# HV_Piezo_Driver.net
KiCad netlist of a schematic drawn in Altium Designer
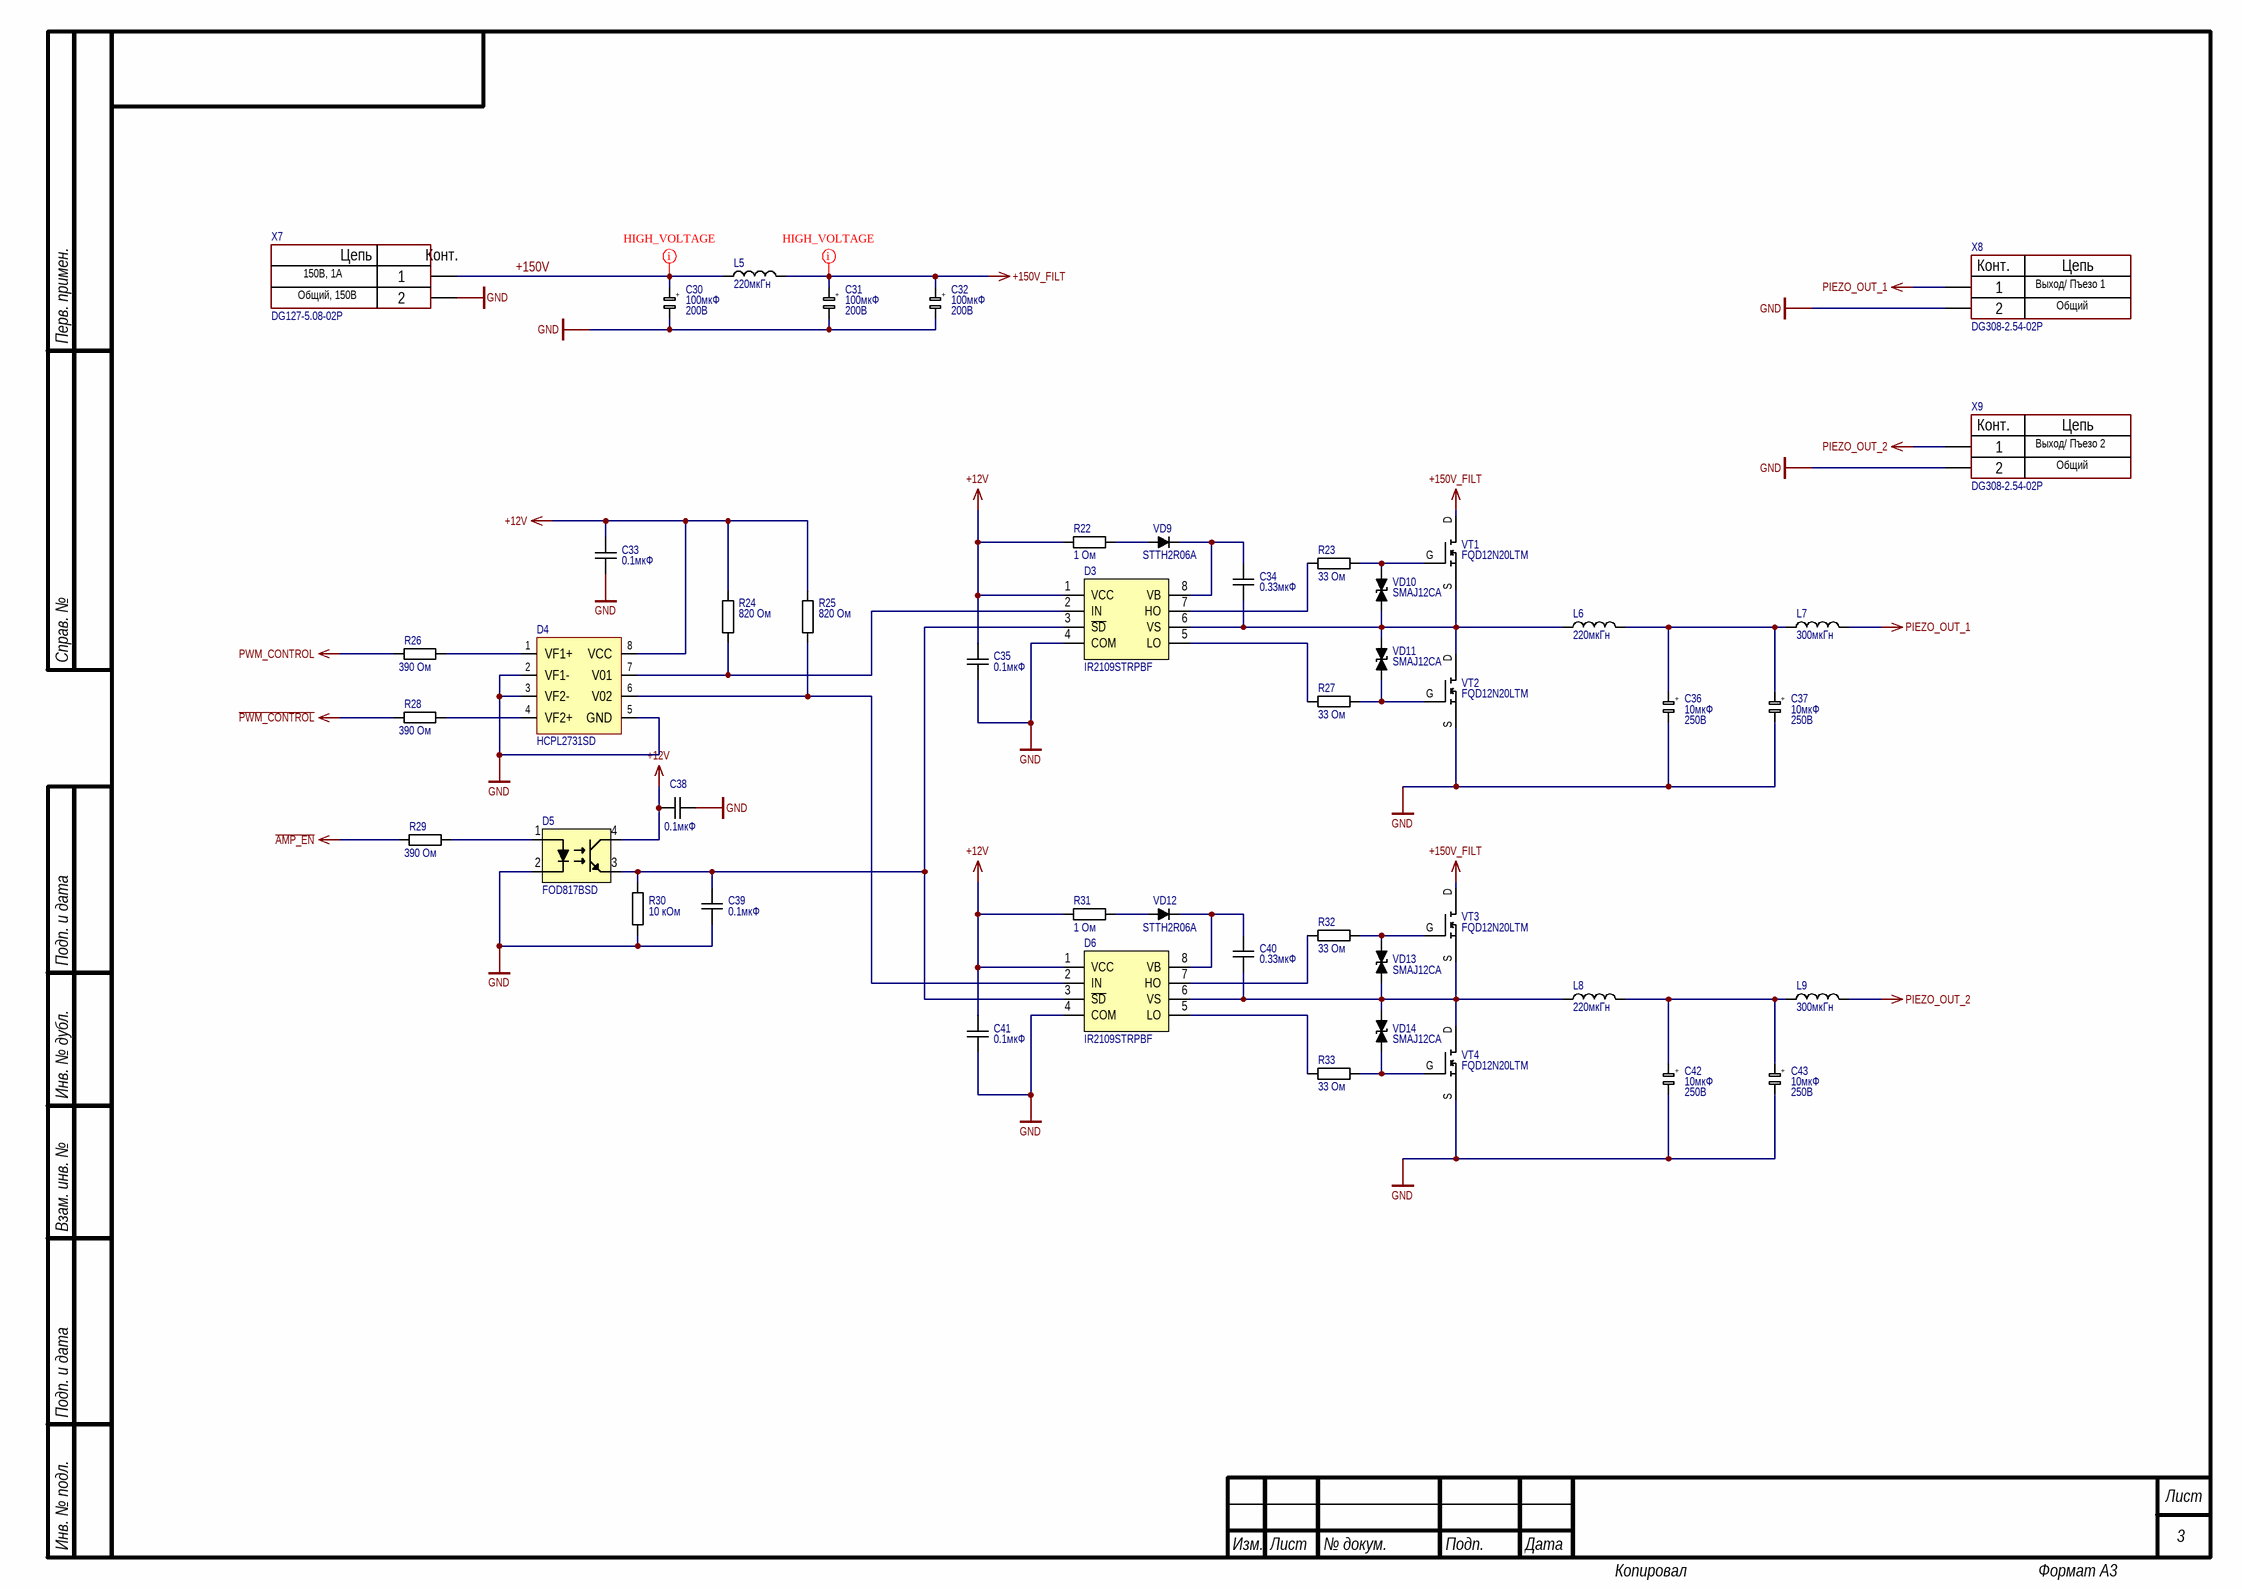
[diagram p0: HV_Piezo_Driver.SchDoc]

(export (version "E")
  (design (tool "Eeschema 10.0.6"))
  (components
    (comp (ref "C30")
      (value "100мкФ")
      (footprint "PiezoControlBoard:CAP_RADIAL_13x17_P5")
      (fields
        (field (name "TOLERANCE") "20%")
        (field (name "VOLTAGE") "200В")
        (field (name "MANUFACTURER PART NUMBER") "JRB2D101M05001300250000B")
        (field (name "Comment") "CAP-100мкФ-20%-200В-105°C-Radial")
      )
      (libsource (lib "PiezoControlBoard") (part "JRB2D101M05001300250000B"))
    )
    (comp (ref "C31")
      (value "100мкФ")
      (footprint "PiezoControlBoard:CAP_RADIAL_13x17_P5")
      (fields
        (field (name "TOLERANCE") "20%")
        (field (name "VOLTAGE") "200В")
        (field (name "MANUFACTURER PART NUMBER") "JRB2D101M05001300250000B")
        (field (name "Comment") "CAP-100мкФ-20%-200В-105°C-Radial")
      )
      (libsource (lib "PiezoControlBoard") (part "JRB2D101M05001300250000B"))
    )
    (comp (ref "C32")
      (value "100мкФ")
      (footprint "PiezoControlBoard:CAP_RADIAL_13x17_P5")
      (fields
        (field (name "TOLERANCE") "20%")
        (field (name "VOLTAGE") "200В")
        (field (name "MANUFACTURER PART NUMBER") "JRB2D101M05001300250000B")
        (field (name "Comment") "CAP-100мкФ-20%-200В-105°C-Radial")
      )
      (libsource (lib "PiezoControlBoard") (part "JRB2D101M05001300250000B"))
    )
    (comp (ref "C33")
      (value "0.1мкФ")
      (footprint "CAP-0603")
      (description "Конденсатор")
      (fields (field (name "TOLERANCE") "10%") (field (name "VOLTAGE") "50В"))
      (libsource (lib "load") (part "Cap_0603"))
    )
    (comp (ref "C34")
      (value "0.33мкФ")
      (footprint "CAP-0805")
      (description "Конденсатор")
      (fields (field (name "TOLERANCE") "10%") (field (name "VOLTAGE") "25В"))
      (libsource (lib "load") (part "Cap_0805"))
    )
    (comp (ref "C35")
      (value "0.1мкФ")
      (footprint "CAP-0603")
      (description "Конденсатор")
      (fields (field (name "TOLERANCE") "10%") (field (name "VOLTAGE") "50В"))
      (libsource (lib "load") (part "Cap_0603"))
    )
    (comp (ref "C36")
      (value "10мкФ")
      (footprint "PiezoControlBoard:CAP_RADIAL_10x20_P5")
      (fields
        (field (name "TOLERANCE") "20%")
        (field (name "MANUFACTURER PART NUMBER") "JRB2E100M05001000170000B")
        (field (name "VOLTAGE") "250В")
        (field (name "Comment") "CAP-10мкФ-20%-250В-105°C-Radial")
      )
      (libsource (lib "PiezoControlBoard") (part "JRB2E100M05001000170000B"))
    )
    (comp (ref "C37")
      (value "10мкФ")
      (footprint "PiezoControlBoard:CAP_RADIAL_10x20_P5")
      (fields
        (field (name "TOLERANCE") "20%")
        (field (name "MANUFACTURER PART NUMBER") "JRB2E100M05001000170000B")
        (field (name "VOLTAGE") "250В")
        (field (name "Comment") "CAP-10мкФ-20%-250В-105°C-Radial")
      )
      (libsource (lib "PiezoControlBoard") (part "JRB2E100M05001000170000B"))
    )
    (comp (ref "C38")
      (value "0.1мкФ")
      (footprint "CAP-0603")
      (description "Конденсатор")
      (fields (field (name "TOLERANCE") "10%") (field (name "VOLTAGE") "50В"))
      (libsource (lib "load") (part "Cap_0603"))
    )
    (comp (ref "C39")
      (value "0.1мкФ")
      (footprint "CAP-0603")
      (description "Конденсатор")
      (fields (field (name "TOLERANCE") "10%") (field (name "VOLTAGE") "50В"))
      (libsource (lib "load") (part "Cap_0603"))
    )
    (comp (ref "C40")
      (value "0.33мкФ")
      (footprint "CAP-0805")
      (description "Конденсатор")
      (fields (field (name "TOLERANCE") "10%") (field (name "VOLTAGE") "25В"))
      (libsource (lib "load") (part "Cap_0805"))
    )
    (comp (ref "C41")
      (value "0.1мкФ")
      (footprint "CAP-0603")
      (description "Конденсатор")
      (fields (field (name "TOLERANCE") "10%") (field (name "VOLTAGE") "50В"))
      (libsource (lib "load") (part "Cap_0603"))
    )
    (comp (ref "C42")
      (value "10мкФ")
      (footprint "PiezoControlBoard:CAP_RADIAL_10x20_P5")
      (fields
        (field (name "TOLERANCE") "20%")
        (field (name "MANUFACTURER PART NUMBER") "JRB2E100M05001000170000B")
        (field (name "VOLTAGE") "250В")
        (field (name "Comment") "CAP-10мкФ-20%-250В-105°C-Radial")
      )
      (libsource (lib "PiezoControlBoard") (part "JRB2E100M05001000170000B"))
    )
    (comp (ref "C43")
      (value "10мкФ")
      (footprint "PiezoControlBoard:CAP_RADIAL_10x20_P5")
      (fields
        (field (name "TOLERANCE") "20%")
        (field (name "MANUFACTURER PART NUMBER") "JRB2E100M05001000170000B")
        (field (name "VOLTAGE") "250В")
        (field (name "Comment") "CAP-10мкФ-20%-250В-105°C-Radial")
      )
      (libsource (lib "PiezoControlBoard") (part "JRB2E100M05001000170000B"))
    )
    (comp (ref "D3")
      (value "IR2109STRPBF")
      (footprint "PiezoControlBoard:SOIC-8")
      (description "Драйвер полумостовой")
      (fields (field (name "POWER") "625mW"))
      (libsource (lib "PiezoControlBoard") (part "IR2109STRPBF"))
    )
    (comp (ref "D4")
      (value "HCPL2731SD")
      (footprint "PiezoControlBoard:SMD-8")
      (description "Оптоизолятор 2.5кВ двухканальный с транзистором Дарлингтона 8SMD")
      (libsource (lib "PiezoControlBoard") (part "HCPL2731SD"))
    )
    (comp (ref "D5")
      (value "FOD817BSD")
      (footprint "PiezoControlBoard:SMD-4")
      (description "Optocoupler, Transistor Output, 1 Channel, Surface Mount DIP, 4 Pins, 50 mA, 5 kV, 130 %")
      (fields (field (name "MANUFACTURER") "onsemi"))
      (libsource (lib "PiezoControlBoard") (part "FOD817BSD"))
    )
    (comp (ref "D6")
      (value "IR2109STRPBF")
      (footprint "PiezoControlBoard:SOIC-8")
      (description "Драйвер полумостовой")
      (fields (field (name "POWER") "625mW"))
      (libsource (lib "PiezoControlBoard") (part "IR2109STRPBF"))
    )
    (comp (ref "L5")
      (value "SPRH127-221M")
      (footprint "PiezoControlBoard:IND_12.3X12.3")
      (description "220мкГн, 2.22А, 12.3х12.3х8 мм, Катушка индуктивности SMD")
      (fields (field (name "INDUCTANCE") "220мкГн"))
      (libsource (lib "PiezoControlBoard") (part "SPRH127-221M"))
    )
    (comp (ref "L6")
      (value "SPRH127-221M")
      (footprint "PiezoControlBoard:IND_12.3X12.3")
      (description "220мкГн, 2.22А, 12.3х12.3х8 мм, Катушка индуктивности SMD")
      (fields (field (name "INDUCTANCE") "220мкГн"))
      (libsource (lib "PiezoControlBoard") (part "SPRH127-221M"))
    )
    (comp (ref "L7")
      (value "SDR0805-331KL")
      (footprint "PiezoControlBoard:IND_7.8X7.8")
      (description "330мкГн, 0.4А, Индуктивность SMD")
      (fields (field (name "INDUCTANCE") "300мкГн"))
      (libsource (lib "PiezoControlBoard") (part "SDR0805-331KL"))
    )
    (comp (ref "L8")
      (value "SPRH127-221M")
      (footprint "PiezoControlBoard:IND_12.3X12.3")
      (description "220мкГн, 2.22А, 12.3х12.3х8 мм, Катушка индуктивности SMD")
      (fields (field (name "INDUCTANCE") "220мкГн"))
      (libsource (lib "PiezoControlBoard") (part "SPRH127-221M"))
    )
    (comp (ref "L9")
      (value "SDR0805-331KL")
      (footprint "PiezoControlBoard:IND_7.8X7.8")
      (description "330мкГн, 0.4А, Индуктивность SMD")
      (fields (field (name "INDUCTANCE") "300мкГн"))
      (libsource (lib "PiezoControlBoard") (part "SDR0805-331KL"))
    )
    (comp (ref "R22")
      (value "1 Ом")
      (footprint "RES-1206")
      (description "Резистор")
      (fields (field (name "TOLERANCE") "5%") (field (name "POWER") "0.25Вт"))
      (libsource (lib "load") (part "Res_1206"))
    )
    (comp (ref "R23")
      (value "33 Ом")
      (footprint "RES-1206")
      (description "Резистор")
      (fields (field (name "TOLERANCE") "5%") (field (name "POWER") "0,25Вт"))
      (libsource (lib "load") (part "Res_1206"))
    )
    (comp (ref "R24")
      (value "820 Ом")
      (footprint "RES-1206")
      (description "Резистор")
      (fields (field (name "TOLERANCE") "5%") (field (name "POWER") "0.25Вт"))
      (libsource (lib "load") (part "Res_1206"))
    )
    (comp (ref "R25")
      (value "820 Ом")
      (footprint "RES-1206")
      (description "Резистор")
      (fields (field (name "TOLERANCE") "5%") (field (name "POWER") "0.25Вт"))
      (libsource (lib "load") (part "Res_1206"))
    )
    (comp (ref "R26")
      (value "390 Ом")
      (footprint "RES-0603")
      (description "Резистор")
      (fields (field (name "POWER") "250мВт") (field (name "TOLERANCE") "5%"))
      (libsource (lib "load") (part "Res_0603"))
    )
    (comp (ref "R27")
      (value "33 Ом")
      (footprint "RES-1206")
      (description "Резистор")
      (fields (field (name "TOLERANCE") "5%") (field (name "POWER") "0,25Вт"))
      (libsource (lib "load") (part "Res_1206"))
    )
    (comp (ref "R28")
      (value "390 Ом")
      (footprint "RES-0603")
      (description "Резистор")
      (fields (field (name "POWER") "250мВт") (field (name "TOLERANCE") "5%"))
      (libsource (lib "load") (part "Res_0603"))
    )
    (comp (ref "R29")
      (value "390 Ом")
      (footprint "RES-0603")
      (description "Резистор")
      (fields (field (name "POWER") "250мВт") (field (name "TOLERANCE") "5%"))
      (libsource (lib "load") (part "Res_0603"))
    )
    (comp (ref "R30")
      (value "10 кОм")
      (footprint "RES-0603")
      (description "Резистор")
      (fields (field (name "POWER") "0.1Вт") (field (name "TOLERANCE") "5%"))
      (libsource (lib "load") (part "Res_0603"))
    )
    (comp (ref "R31")
      (value "1 Ом")
      (footprint "RES-1206")
      (description "Резистор")
      (fields (field (name "TOLERANCE") "5%") (field (name "POWER") "0.25Вт"))
      (libsource (lib "load") (part "Res_1206"))
    )
    (comp (ref "R32")
      (value "33 Ом")
      (footprint "RES-1206")
      (description "Резистор")
      (fields (field (name "TOLERANCE") "5%") (field (name "POWER") "0,25Вт"))
      (libsource (lib "load") (part "Res_1206"))
    )
    (comp (ref "R33")
      (value "33 Ом")
      (footprint "RES-1206")
      (description "Резистор")
      (fields (field (name "TOLERANCE") "5%") (field (name "POWER") "0,25Вт"))
      (libsource (lib "load") (part "Res_1206"))
    )
    (comp (ref "VD9")
      (value "STTH2R06A")
      (footprint "PiezoControlBoard:SMA")
      (description "Rectifier Diode, 1 Phase, 1 Element, 2A, 600V V(RRM), Silicon")
      (fields (field (name "MANUFACTURER") "STMicroelectronics"))
      (libsource (lib "PiezoControlBoard") (part "STTH2R06A"))
    )
    (comp (ref "VD10")
      (value "SMAJ12CA")
      (footprint "PiezoControlBoard:DO-214AC")
      (description "Диод защитный от перенапряжения - TVS (супрессор) 12В включение 19.9В ограничение SMA")
      (libsource (lib "PiezoControlBoard") (part "SMAJ12CA"))
    )
    (comp (ref "VD11")
      (value "SMAJ12CA")
      (footprint "PiezoControlBoard:DO-214AC")
      (description "Диод защитный от перенапряжения - TVS (супрессор) 12В включение 19.9В ограничение SMA")
      (libsource (lib "PiezoControlBoard") (part "SMAJ12CA"))
    )
    (comp (ref "VD12")
      (value "STTH2R06A")
      (footprint "PiezoControlBoard:SMA")
      (description "Rectifier Diode, 1 Phase, 1 Element, 2A, 600V V(RRM), Silicon")
      (fields (field (name "MANUFACTURER") "STMicroelectronics"))
      (libsource (lib "PiezoControlBoard") (part "STTH2R06A"))
    )
    (comp (ref "VD13")
      (value "SMAJ12CA")
      (footprint "PiezoControlBoard:DO-214AC")
      (description "Диод защитный от перенапряжения - TVS (супрессор) 12В включение 19.9В ограничение SMA")
      (libsource (lib "PiezoControlBoard") (part "SMAJ12CA"))
    )
    (comp (ref "VD14")
      (value "SMAJ12CA")
      (footprint "PiezoControlBoard:DO-214AC")
      (description "Диод защитный от перенапряжения - TVS (супрессор) 12В включение 19.9В ограничение SMA")
      (libsource (lib "PiezoControlBoard") (part "SMAJ12CA"))
    )
    (comp (ref "VT1")
      (value "FQD12N20LTM")
      (footprint "PiezoControlBoard:DPAK3")
      (libsource (lib "PiezoControlBoard") (part "FQD12N20LTM"))
    )
    (comp (ref "VT2")
      (value "FQD12N20LTM")
      (footprint "PiezoControlBoard:DPAK3")
      (libsource (lib "PiezoControlBoard") (part "FQD12N20LTM"))
    )
    (comp (ref "VT3")
      (value "FQD12N20LTM")
      (footprint "PiezoControlBoard:DPAK3")
      (libsource (lib "PiezoControlBoard") (part "FQD12N20LTM"))
    )
    (comp (ref "VT4")
      (value "FQD12N20LTM")
      (footprint "PiezoControlBoard:DPAK3")
      (libsource (lib "PiezoControlBoard") (part "FQD12N20LTM"))
    )
    (comp (ref "X7")
      (value "DG127-5.08-02P")
      (footprint "PiezoControlBoard:DG12750802P141000AH")
      (fields (field (name "CURCIUT 2") "Общий, 150В") (field (name "CURCIUT 1") "150В, 1А"))
      (libsource (lib "PiezoControlBoard") (part "DG127-5.08-02P"))
    )
    (comp (ref "X8")
      (value "DG308-2.54-02P")
      (footprint "PiezoControlBoard:DG30825402P1400AH")
      (fields (field (name "CURCIUT 2") "Общий") (field (name "CURCIUT 1") "Выход/ Пъезо 1"))
      (libsource (lib "PiezoControlBoard") (part "DG308-2.54-02P"))
    )
    (comp (ref "X9")
      (value "DG308-2.54-02P")
      (footprint "PiezoControlBoard:DG30825402P1400AH")
      (fields (field (name "CURCIUT 2") "Общий") (field (name "CURCIUT 1") "Выход/ Пъезо 2"))
      (libsource (lib "PiezoControlBoard") (part "DG308-2.54-02P"))
    )
  )
  (nets
    (net (code "1") (name "+12V") (class "Default")
      (node (ref "C33") (pin "2") (pinfunction "2_2") (pintype "passive"))
      (node (ref "C35") (pin "2") (pinfunction "2_2") (pintype "passive"))
      (node (ref "C38") (pin "2") (pinfunction "2_2") (pintype "passive"))
      (node (ref "C41") (pin "2") (pinfunction "2_2") (pintype "passive"))
      (node (ref "D3") (pin "1") (pinfunction "VCC_1") (pintype "power_in"))
      (node (ref "D4") (pin "8") (pinfunction "VCC_8") (pintype "passive"))
      (node (ref "D5") (pin "4") (pinfunction "COLLECTOR_4") (pintype "passive"))
      (node (ref "D6") (pin "1") (pinfunction "VCC_1") (pintype "power_in"))
      (node (ref "R22") (pin "1") (pinfunction "1_1") (pintype "passive"))
      (node (ref "R24") (pin "2") (pinfunction "2_2") (pintype "passive"))
      (node (ref "R25") (pin "2") (pinfunction "2_2") (pintype "passive"))
      (node (ref "R31") (pin "1") (pinfunction "1_1") (pintype "passive"))
    )
    (net (code "2") (name "+150V_FILT") (class "Default")
      (node (ref "C31") (pin "P") (pinfunction "P_P") (pintype "passive"))
      (node (ref "C32") (pin "P") (pinfunction "P_P") (pintype "passive"))
      (node (ref "L5") (pin "2") (pinfunction "2_2") (pintype "passive"))
      (node (ref "VT1") (pin "D") (pinfunction "D_D") (pintype "passive"))
      (node (ref "VT3") (pin "D") (pinfunction "D_D") (pintype "passive"))
    )
    (net (code "3") (name "/+150V") (class "Default")
      (node (ref "C30") (pin "P") (pinfunction "P_P") (pintype "passive"))
      (node (ref "L5") (pin "1") (pinfunction "1_1") (pintype "passive"))
      (node (ref "X7") (pin "1") (pinfunction "1_1") (pintype "passive"))
    )
    (net (code "4") (name "GND") (class "Default")
      (node (ref "C30") (pin "N") (pinfunction "N_N") (pintype "passive"))
      (node (ref "C31") (pin "N") (pinfunction "N_N") (pintype "passive"))
      (node (ref "C32") (pin "N") (pinfunction "N_N") (pintype "passive"))
      (node (ref "C33") (pin "1") (pinfunction "1_1") (pintype "passive"))
      (node (ref "C35") (pin "1") (pinfunction "1_1") (pintype "passive"))
      (node (ref "C36") (pin "N") (pinfunction "N_N") (pintype "passive"))
      (node (ref "C37") (pin "N") (pinfunction "N_N") (pintype "passive"))
      (node (ref "C38") (pin "1") (pinfunction "1_1") (pintype "passive"))
      (node (ref "C39") (pin "1") (pinfunction "1_1") (pintype "passive"))
      (node (ref "C41") (pin "1") (pinfunction "1_1") (pintype "passive"))
      (node (ref "C42") (pin "N") (pinfunction "N_N") (pintype "passive"))
      (node (ref "C43") (pin "N") (pinfunction "N_N") (pintype "passive"))
      (node (ref "D3") (pin "4") (pinfunction "COM_4") (pintype "passive"))
      (node (ref "D4") (pin "2") (pinfunction "VF1-_2") (pintype "passive"))
      (node (ref "D4") (pin "3") (pinfunction "VF2-_3") (pintype "passive"))
      (node (ref "D4") (pin "5") (pinfunction "GND_5") (pintype "passive"))
      (node (ref "D5") (pin "2") (pinfunction "CATHODE_2") (pintype "passive"))
      (node (ref "D6") (pin "4") (pinfunction "COM_4") (pintype "passive"))
      (node (ref "R30") (pin "1") (pinfunction "1_1") (pintype "passive"))
      (node (ref "VT2") (pin "S") (pinfunction "S_S") (pintype "passive"))
      (node (ref "VT4") (pin "S") (pinfunction "S_S") (pintype "passive"))
      (node (ref "X7") (pin "2") (pinfunction "2_2") (pintype "passive"))
      (node (ref "X8") (pin "2") (pinfunction "2_2") (pintype "passive"))
      (node (ref "X9") (pin "2") (pinfunction "2_2") (pintype "passive"))
    )
    (net (code "5") (name "Net-(C36-PadP)") (class "Default")
      (node (ref "C36") (pin "P") (pinfunction "P_P") (pintype "passive"))
      (node (ref "C37") (pin "P") (pinfunction "P_P") (pintype "passive"))
      (node (ref "L6") (pin "2") (pinfunction "2_2") (pintype "passive"))
      (node (ref "L7") (pin "1") (pinfunction "1_1") (pintype "passive"))
    )
    (net (code "6") (name "Net-(C42-PadP)") (class "Default")
      (node (ref "C42") (pin "P") (pinfunction "P_P") (pintype "passive"))
      (node (ref "C43") (pin "P") (pinfunction "P_P") (pintype "passive"))
      (node (ref "L8") (pin "2") (pinfunction "2_2") (pintype "passive"))
      (node (ref "L9") (pin "1") (pinfunction "1_1") (pintype "passive"))
    )
    (net (code "7") (name "Net-(D3-HO)") (class "Default")
      (node (ref "D3") (pin "7") (pinfunction "HO_7") (pintype "passive"))
      (node (ref "R23") (pin "1") (pinfunction "1_1") (pintype "passive"))
    )
    (net (code "8") (name "Net-(D3-IN)") (class "Default")
      (node (ref "D3") (pin "2") (pinfunction "IN_2") (pintype "passive"))
      (node (ref "D4") (pin "7") (pinfunction "V01_7") (pintype "passive"))
      (node (ref "R24") (pin "1") (pinfunction "1_1") (pintype "passive"))
    )
    (net (code "9") (name "Net-(D3-LO)") (class "Default")
      (node (ref "D3") (pin "5") (pinfunction "LO_5") (pintype "passive"))
      (node (ref "R27") (pin "1") (pinfunction "1_1") (pintype "passive"))
    )
    (net (code "10") (name "Net-(D3-VB)") (class "Default")
      (node (ref "C34") (pin "2") (pinfunction "2_2") (pintype "passive"))
      (node (ref "D3") (pin "8") (pinfunction "VB_8") (pintype "passive"))
      (node (ref "VD9") (pin "2") (pinfunction "A_2") (pintype "passive"))
    )
    (net (code "11") (name "Net-(D3-VS)") (class "Default")
      (node (ref "C34") (pin "1") (pinfunction "1_1") (pintype "passive"))
      (node (ref "D3") (pin "6") (pinfunction "VS_6") (pintype "passive"))
      (node (ref "L6") (pin "1") (pinfunction "1_1") (pintype "passive"))
      (node (ref "VD10") (pin "C") (pinfunction "C_C") (pintype "passive"))
      (node (ref "VD11") (pin "A") (pinfunction "A_A") (pintype "passive"))
      (node (ref "VT1") (pin "S") (pinfunction "S_S") (pintype "passive"))
      (node (ref "VT2") (pin "D") (pinfunction "D_D") (pintype "passive"))
    )
    (net (code "12") (name "Net-(D3-~{SD})") (class "Default")
      (node (ref "C39") (pin "2") (pinfunction "2_2") (pintype "passive"))
      (node (ref "D3") (pin "3") (pinfunction "~{SD}_3") (pintype "passive"))
      (node (ref "D5") (pin "3") (pinfunction "EMITTER_3") (pintype "passive"))
      (node (ref "D6") (pin "3") (pinfunction "~{SD}_3") (pintype "passive"))
      (node (ref "R30") (pin "2") (pinfunction "2_2") (pintype "passive"))
    )
    (net (code "13") (name "Net-(D4-V02)") (class "Default")
      (node (ref "D4") (pin "6") (pinfunction "V02_6") (pintype "passive"))
      (node (ref "D6") (pin "2") (pinfunction "IN_2") (pintype "passive"))
      (node (ref "R25") (pin "1") (pinfunction "1_1") (pintype "passive"))
    )
    (net (code "14") (name "Net-(D4-VF1+)") (class "Default")
      (node (ref "D4") (pin "1") (pinfunction "VF1+_1") (pintype "passive"))
      (node (ref "R26") (pin "2") (pinfunction "2_2") (pintype "passive"))
    )
    (net (code "15") (name "Net-(D4-VF2+)") (class "Default")
      (node (ref "D4") (pin "4") (pinfunction "VF2+_4") (pintype "passive"))
      (node (ref "R28") (pin "2") (pinfunction "2_2") (pintype "passive"))
    )
    (net (code "16") (name "Net-(D5-ANODE)") (class "Default")
      (node (ref "D5") (pin "1") (pinfunction "ANODE_1") (pintype "passive"))
      (node (ref "R29") (pin "2") (pinfunction "2_2") (pintype "passive"))
    )
    (net (code "17") (name "Net-(D6-HO)") (class "Default")
      (node (ref "D6") (pin "7") (pinfunction "HO_7") (pintype "passive"))
      (node (ref "R32") (pin "1") (pinfunction "1_1") (pintype "passive"))
    )
    (net (code "18") (name "Net-(D6-LO)") (class "Default")
      (node (ref "D6") (pin "5") (pinfunction "LO_5") (pintype "passive"))
      (node (ref "R33") (pin "1") (pinfunction "1_1") (pintype "passive"))
    )
    (net (code "19") (name "Net-(D6-VB)") (class "Default")
      (node (ref "C40") (pin "2") (pinfunction "2_2") (pintype "passive"))
      (node (ref "D6") (pin "8") (pinfunction "VB_8") (pintype "passive"))
      (node (ref "VD12") (pin "2") (pinfunction "A_2") (pintype "passive"))
    )
    (net (code "20") (name "Net-(D6-VS)") (class "Default")
      (node (ref "C40") (pin "1") (pinfunction "1_1") (pintype "passive"))
      (node (ref "D6") (pin "6") (pinfunction "VS_6") (pintype "passive"))
      (node (ref "L8") (pin "1") (pinfunction "1_1") (pintype "passive"))
      (node (ref "VD13") (pin "C") (pinfunction "C_C") (pintype "passive"))
      (node (ref "VD14") (pin "A") (pinfunction "A_A") (pintype "passive"))
      (node (ref "VT3") (pin "S") (pinfunction "S_S") (pintype "passive"))
      (node (ref "VT4") (pin "D") (pinfunction "D_D") (pintype "passive"))
    )
    (net (code "21") (name "Net-(R23-Pad2)") (class "Default")
      (node (ref "R23") (pin "2") (pinfunction "2_2") (pintype "passive"))
      (node (ref "VD10") (pin "A") (pinfunction "A_A") (pintype "passive"))
      (node (ref "VT1") (pin "G") (pinfunction "G_G") (pintype "passive"))
    )
    (net (code "22") (name "Net-(R27-Pad2)") (class "Default")
      (node (ref "R27") (pin "2") (pinfunction "2_2") (pintype "passive"))
      (node (ref "VD11") (pin "C") (pinfunction "C_C") (pintype "passive"))
      (node (ref "VT2") (pin "G") (pinfunction "G_G") (pintype "passive"))
    )
    (net (code "23") (name "Net-(R32-Pad2)") (class "Default")
      (node (ref "R32") (pin "2") (pinfunction "2_2") (pintype "passive"))
      (node (ref "VD13") (pin "A") (pinfunction "A_A") (pintype "passive"))
      (node (ref "VT3") (pin "G") (pinfunction "G_G") (pintype "passive"))
    )
    (net (code "24") (name "Net-(R33-Pad2)") (class "Default")
      (node (ref "R33") (pin "2") (pinfunction "2_2") (pintype "passive"))
      (node (ref "VD14") (pin "C") (pinfunction "C_C") (pintype "passive"))
      (node (ref "VT4") (pin "G") (pinfunction "G_G") (pintype "passive"))
    )
    (net (code "25") (name "Net-(VD9-K)") (class "Default")
      (node (ref "R22") (pin "2") (pinfunction "2_2") (pintype "passive"))
      (node (ref "VD9") (pin "1") (pinfunction "K_1") (pintype "passive"))
    )
    (net (code "26") (name "Net-(VD12-K)") (class "Default")
      (node (ref "R31") (pin "2") (pinfunction "2_2") (pintype "passive"))
      (node (ref "VD12") (pin "1") (pinfunction "K_1") (pintype "passive"))
    )
    (net (code "27") (name "PIEZO_OUT_1") (class "Default")
      (node (ref "L7") (pin "2") (pinfunction "2_2") (pintype "passive"))
      (node (ref "X8") (pin "1") (pinfunction "1_1") (pintype "passive"))
    )
    (net (code "28") (name "PIEZO_OUT_2") (class "Default")
      (node (ref "L9") (pin "2") (pinfunction "2_2") (pintype "passive"))
      (node (ref "X9") (pin "1") (pinfunction "1_1") (pintype "passive"))
    )
    (net (code "29") (name "PWM_CONTROL") (class "Default")
      (node (ref "R26") (pin "1") (pinfunction "1_1") (pintype "passive"))
    )
    (net (code "30") (name "~{AMP_EN}") (class "Default")
      (node (ref "R29") (pin "1") (pinfunction "1_1") (pintype "passive"))
    )
    (net (code "31") (name "~{PWM_CONTROL}") (class "Default")
      (node (ref "R28") (pin "1") (pinfunction "1_1") (pintype "passive"))
    )
  )
)
